# ZGAD250D12.net
KiCad netlist of a schematic drawn in Altium Designer
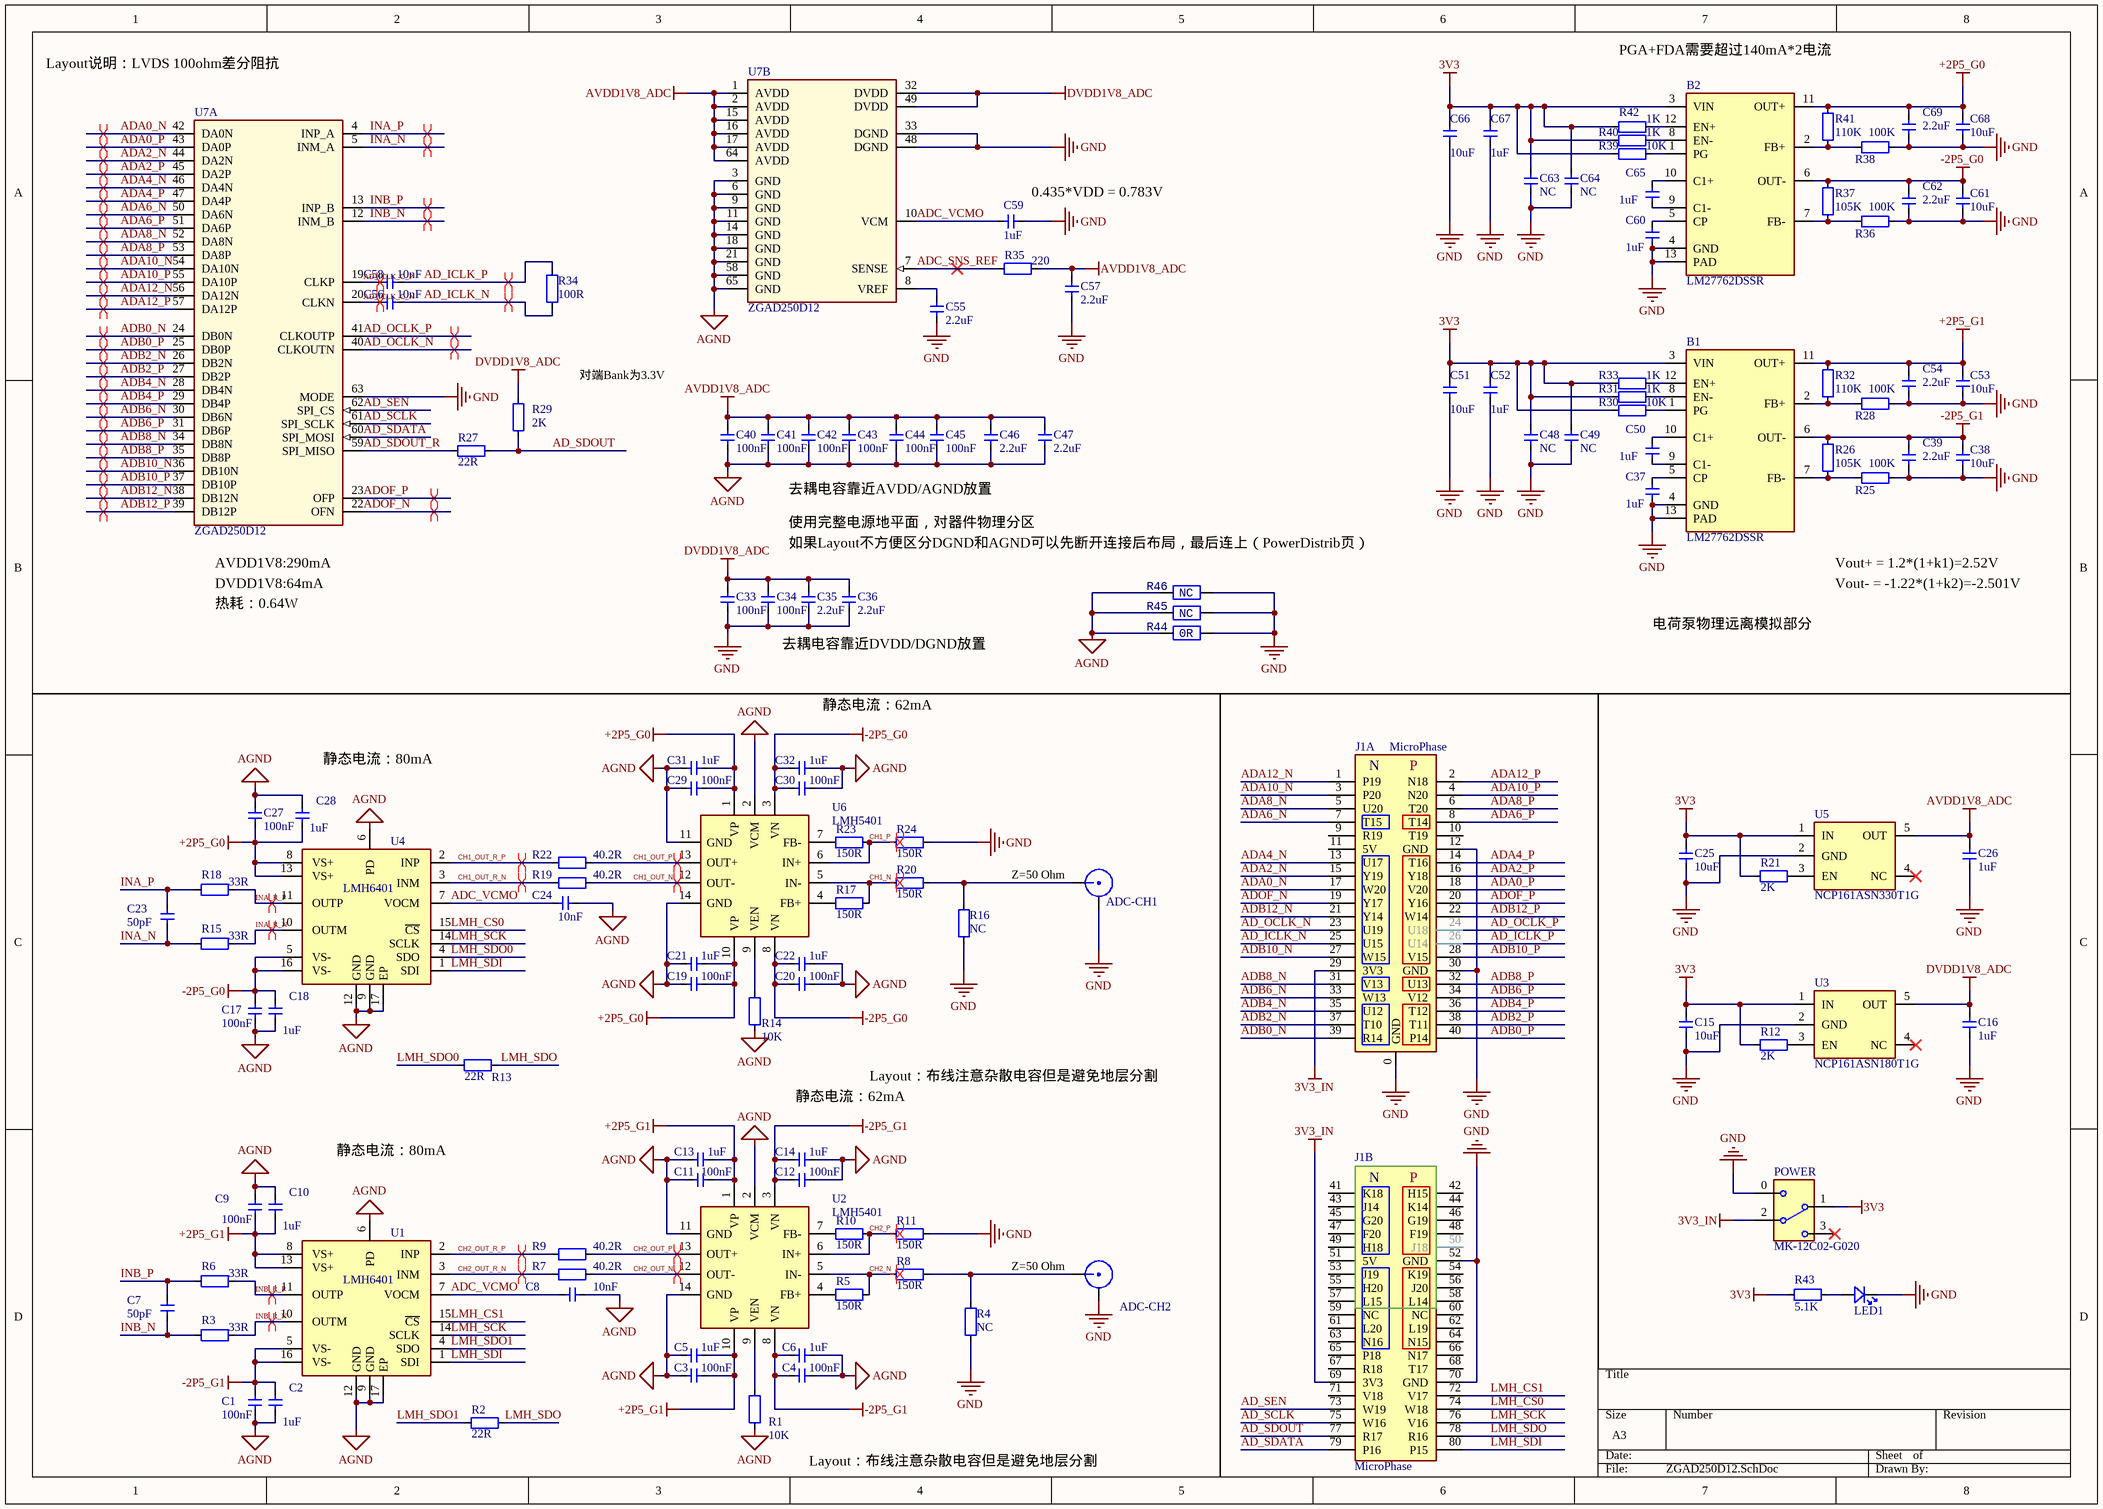
[diagram p0: ZGAD250D12.SchDoc]

(export (version "E")
  (design (tool "Eeschema 10.0.6"))
  (components
    (comp (ref "ADC-CH1")
      (value "SMA")
      (footprint "SMA-KHD")
      (description "SMA射频接口")
      (libsource (lib "Base") (part "SMA"))
    )
    (comp (ref "ADC-CH2")
      (value "SMA")
      (footprint "SMA-KHD")
      (description "SMA射频接口")
      (libsource (lib "Base") (part "SMA"))
    )
    (comp (ref "B1")
      (value "LM27762DSSR")
      (footprint "SON50P200X300X80-13N-D")
      (fields (field (name "MOUSER PART NUMBER") "595-LM27762DSSR"))
      (libsource (lib "Power") (part "LM27762DSSR"))
    )
    (comp (ref "B2")
      (value "LM27762DSSR")
      (footprint "SON50P200X300X80-13N-D")
      (fields (field (name "MOUSER PART NUMBER") "595-LM27762DSSR"))
      (libsource (lib "Power") (part "LM27762DSSR"))
    )
    (comp (ref "C1")
      (value "100nF")
      (footprint "C 0201")
      (description "GRM033Z71C104KE14D")
      (fields (field (name "版权归属") "源创客"))
      (libsource (lib "Base") (part "C"))
    )
    (comp (ref "C2")
      (value "1uF")
      (footprint "C 0402")
      (description "GRM155Z71A105KE01D")
      (fields (field (name "版权归属") "源创客"))
      (libsource (lib "Base") (part "C"))
    )
    (comp (ref "C3")
      (value "100nF")
      (footprint "C 0201")
      (description "GRM033Z71C104KE14D")
      (fields (field (name "版权归属") "源创客"))
      (libsource (lib "Base") (part "C"))
    )
    (comp (ref "C4")
      (value "100nF")
      (footprint "C 0201")
      (description "GRM033Z71C104KE14D")
      (fields (field (name "版权归属") "源创客"))
      (libsource (lib "Base") (part "C"))
    )
    (comp (ref "C5")
      (value "1uF")
      (footprint "C 0402")
      (description "GRM155Z71A105KE01D")
      (fields (field (name "版权归属") "源创客"))
      (libsource (lib "Base") (part "C"))
    )
    (comp (ref "C6")
      (value "1uF")
      (footprint "C 0402")
      (description "GRM155Z71A105KE01D")
      (fields (field (name "版权归属") "源创客"))
      (libsource (lib "Base") (part "C"))
    )
    (comp (ref "C7")
      (value "50pF")
      (footprint "C 0201")
      (description "0603CG500J500NT")
      (fields (field (name "版权归属") "源创客"))
      (libsource (lib "Base") (part "C"))
    )
    (comp (ref "C8")
      (value "10nF")
      (footprint "C 0201")
      (description "0201B103K250NT")
      (fields (field (name "版权归属") "源创客"))
      (libsource (lib "Base") (part "C"))
    )
    (comp (ref "C9")
      (value "100nF")
      (footprint "C 0201")
      (description "GRM033Z71C104KE14D")
      (fields (field (name "版权归属") "源创客"))
      (libsource (lib "Base") (part "C"))
    )
    (comp (ref "C10")
      (value "1uF")
      (footprint "C 0402")
      (description "GRM155Z71A105KE01D")
      (fields (field (name "版权归属") "源创客"))
      (libsource (lib "Base") (part "C"))
    )
    (comp (ref "C11")
      (value "100nF")
      (footprint "C 0201")
      (description "GRM033Z71C104KE14D")
      (fields (field (name "版权归属") "源创客"))
      (libsource (lib "Base") (part "C"))
    )
    (comp (ref "C12")
      (value "100nF")
      (footprint "C 0201")
      (description "GRM033Z71C104KE14D")
      (fields (field (name "版权归属") "源创客"))
      (libsource (lib "Base") (part "C"))
    )
    (comp (ref "C13")
      (value "1uF")
      (footprint "C 0402")
      (description "GRM155Z71A105KE01D")
      (fields (field (name "版权归属") "源创客"))
      (libsource (lib "Base") (part "C"))
    )
    (comp (ref "C14")
      (value "1uF")
      (footprint "C 0402")
      (description "GRM155Z71A105KE01D")
      (fields (field (name "版权归属") "源创客"))
      (libsource (lib "Base") (part "C"))
    )
    (comp (ref "C15")
      (value "10uF")
      (footprint "C 0603")
      (description "无极性贴片电容")
      (fields (field (name "版权归属") "源创客"))
      (libsource (lib "Base") (part "C"))
    )
    (comp (ref "C16")
      (value "1uF")
      (footprint "C 0402")
      (description "无极性贴片电容")
      (fields (field (name "版权归属") "源创客"))
      (libsource (lib "Base") (part "C"))
    )
    (comp (ref "C17")
      (value "100nF")
      (footprint "C 0201")
      (description "GRM033Z71C104KE14D")
      (fields (field (name "版权归属") "源创客"))
      (libsource (lib "Base") (part "C"))
    )
    (comp (ref "C18")
      (value "1uF")
      (footprint "C 0402")
      (description "GRM155Z71A105KE01D")
      (fields (field (name "版权归属") "源创客"))
      (libsource (lib "Base") (part "C"))
    )
    (comp (ref "C19")
      (value "100nF")
      (footprint "C 0201")
      (description "GRM033Z71C104KE14D")
      (fields (field (name "版权归属") "源创客"))
      (libsource (lib "Base") (part "C"))
    )
    (comp (ref "C20")
      (value "100nF")
      (footprint "C 0201")
      (description "GRM033Z71C104KE14D")
      (fields (field (name "版权归属") "源创客"))
      (libsource (lib "Base") (part "C"))
    )
    (comp (ref "C21")
      (value "1uF")
      (footprint "C 0402")
      (description "GRM155Z71A105KE01D")
      (fields (field (name "版权归属") "源创客"))
      (libsource (lib "Base") (part "C"))
    )
    (comp (ref "C22")
      (value "1uF")
      (footprint "C 0402")
      (description "GRM155Z71A105KE01D")
      (fields (field (name "版权归属") "源创客"))
      (libsource (lib "Base") (part "C"))
    )
    (comp (ref "C23")
      (value "50pF")
      (footprint "C 0201")
      (description "0603CG500J500NT")
      (fields (field (name "版权归属") "源创客"))
      (libsource (lib "Base") (part "C"))
    )
    (comp (ref "C24")
      (value "10nF")
      (footprint "C 0201")
      (description "0201B103K250NT")
      (fields (field (name "版权归属") "源创客"))
      (libsource (lib "Base") (part "C"))
    )
    (comp (ref "C25")
      (value "10uF")
      (footprint "C 0603")
      (description "无极性贴片电容")
      (fields (field (name "版权归属") "源创客"))
      (libsource (lib "Base") (part "C"))
    )
    (comp (ref "C26")
      (value "1uF")
      (footprint "C 0402")
      (description "无极性贴片电容")
      (fields (field (name "版权归属") "源创客"))
      (libsource (lib "Base") (part "C"))
    )
    (comp (ref "C27")
      (value "100nF")
      (footprint "C 0201")
      (description "GRM033Z71C104KE14D")
      (fields (field (name "版权归属") "源创客"))
      (libsource (lib "Base") (part "C"))
    )
    (comp (ref "C28")
      (value "1uF")
      (footprint "C 0402")
      (description "GRM155Z71A105KE01D")
      (fields (field (name "版权归属") "源创客"))
      (libsource (lib "Base") (part "C"))
    )
    (comp (ref "C29")
      (value "100nF")
      (footprint "C 0201")
      (description "GRM033Z71C104KE14D")
      (fields (field (name "版权归属") "源创客"))
      (libsource (lib "Base") (part "C"))
    )
    (comp (ref "C30")
      (value "100nF")
      (footprint "C 0201")
      (description "GRM033Z71C104KE14D")
      (fields (field (name "版权归属") "源创客"))
      (libsource (lib "Base") (part "C"))
    )
    (comp (ref "C31")
      (value "1uF")
      (footprint "C 0402")
      (description "GRM155Z71A105KE01D")
      (fields (field (name "版权归属") "源创客"))
      (libsource (lib "Base") (part "C"))
    )
    (comp (ref "C32")
      (value "1uF")
      (footprint "C 0402")
      (description "GRM155Z71A105KE01D")
      (fields (field (name "版权归属") "源创客"))
      (libsource (lib "Base") (part "C"))
    )
    (comp (ref "C33")
      (value "100nF")
      (footprint "C 0201")
      (description "GRM033Z71C104KE14D")
      (fields (field (name "版权归属") "源创客"))
      (libsource (lib "Base") (part "C"))
    )
    (comp (ref "C34")
      (value "100nF")
      (footprint "C 0201")
      (description "GRM033Z71C104KE14D")
      (fields (field (name "版权归属") "源创客"))
      (libsource (lib "Base") (part "C"))
    )
    (comp (ref "C35")
      (value "2.2uF")
      (footprint "C 0603")
      (description "0603B225K250NT")
      (fields (field (name "版权归属") "源创客"))
      (libsource (lib "Base") (part "C"))
    )
    (comp (ref "C36")
      (value "2.2uF")
      (footprint "C 0603")
      (description "0603B225K250NT")
      (fields (field (name "版权归属") "源创客"))
      (libsource (lib "Base") (part "C"))
    )
    (comp (ref "C37")
      (value "1uF")
      (footprint "C 0402")
      (description "GRM155Z71A105KE01D")
      (fields (field (name "版权归属") "源创客"))
      (libsource (lib "Base") (part "C"))
    )
    (comp (ref "C38")
      (value "10uF")
      (footprint "C 0603")
      (description "GRM188Z71A106KA73D")
      (fields (field (name "版权归属") "源创客"))
      (libsource (lib "Base") (part "C"))
    )
    (comp (ref "C39")
      (value "2.2uF")
      (footprint "C 0402")
      (description "GRM155Z71A225KE44D")
      (fields (field (name "版权归属") "源创客"))
      (libsource (lib "Base") (part "C"))
    )
    (comp (ref "C40")
      (value "100nF")
      (footprint "C 0201")
      (description "GRM033Z71C104KE14D")
      (fields (field (name "版权归属") "源创客"))
      (libsource (lib "Base") (part "C"))
    )
    (comp (ref "C41")
      (value "100nF")
      (footprint "C 0201")
      (description "GRM033Z71C104KE14D")
      (fields (field (name "版权归属") "源创客"))
      (libsource (lib "Base") (part "C"))
    )
    (comp (ref "C42")
      (value "100nF")
      (footprint "C 0201")
      (description "GRM033Z71C104KE14D")
      (fields (field (name "版权归属") "源创客"))
      (libsource (lib "Base") (part "C"))
    )
    (comp (ref "C43")
      (value "100nF")
      (footprint "C 0201")
      (description "GRM033Z71C104KE14D")
      (fields (field (name "版权归属") "源创客"))
      (libsource (lib "Base") (part "C"))
    )
    (comp (ref "C44")
      (value "100nF")
      (footprint "C 0201")
      (description "GRM033Z71C104KE14D")
      (fields (field (name "版权归属") "源创客"))
      (libsource (lib "Base") (part "C"))
    )
    (comp (ref "C45")
      (value "100nF")
      (footprint "C 0201")
      (description "GRM033Z71C104KE14D")
      (fields (field (name "版权归属") "源创客"))
      (libsource (lib "Base") (part "C"))
    )
    (comp (ref "C46")
      (value "2.2uF")
      (footprint "C 0603")
      (description "0603B225K250NT")
      (fields (field (name "版权归属") "源创客"))
      (libsource (lib "Base") (part "C"))
    )
    (comp (ref "C47")
      (value "2.2uF")
      (footprint "C 0603")
      (description "0603B225K250NT")
      (fields (field (name "版权归属") "源创客"))
      (libsource (lib "Base") (part "C"))
    )
    (comp (ref "C48")
      (value "NC")
      (footprint "C 0201")
      (description "GRM033Z71C104KE14D")
      (fields (field (name "版权归属") "源创客"))
      (libsource (lib "Base") (part "C"))
    )
    (comp (ref "C49")
      (value "NC")
      (footprint "C 0201")
      (description "GRM033Z71C104KE14D")
      (fields (field (name "版权归属") "源创客"))
      (libsource (lib "Base") (part "C"))
    )
    (comp (ref "C50")
      (value "1uF")
      (footprint "C 0402")
      (description "GRM155Z71A105KE01D")
      (fields (field (name "版权归属") "源创客"))
      (libsource (lib "Base") (part "C"))
    )
    (comp (ref "C51")
      (value "10uF")
      (footprint "C 0603")
      (description "GRM188Z71A106KA73D")
      (fields (field (name "版权归属") "源创客"))
      (libsource (lib "Base") (part "C"))
    )
    (comp (ref "C52")
      (value "1uF")
      (footprint "C 0402")
      (description "GRM155Z71A105KE01D")
      (fields (field (name "版权归属") "源创客"))
      (libsource (lib "Base") (part "C"))
    )
    (comp (ref "C53")
      (value "10uF")
      (footprint "C 0603")
      (description "GRM188Z71A106KA73D")
      (fields (field (name "版权归属") "源创客"))
      (libsource (lib "Base") (part "C"))
    )
    (comp (ref "C54")
      (value "2.2uF")
      (footprint "C 0402")
      (description "GRM155Z71A225KE44D")
      (fields (field (name "版权归属") "源创客"))
      (libsource (lib "Base") (part "C"))
    )
    (comp (ref "C55")
      (value "2.2uF")
      (footprint "C 0603")
      (description "0603B225K250NT")
      (fields (field (name "版权归属") "源创客"))
      (libsource (lib "Base") (part "C"))
    )
    (comp (ref "C56")
      (value "10nF")
      (footprint "C 0201")
      (description "0201B103K250NT")
      (fields (field (name "版权归属") "源创客"))
      (libsource (lib "Base") (part "C"))
    )
    (comp (ref "C57")
      (value "2.2uF")
      (footprint "C 0603")
      (description "0603B225K250NT")
      (fields (field (name "版权归属") "源创客"))
      (libsource (lib "Base") (part "C"))
    )
    (comp (ref "C58")
      (value "10nF")
      (footprint "C 0201")
      (description "0201B103K250NT")
      (fields (field (name "版权归属") "源创客"))
      (libsource (lib "Base") (part "C"))
    )
    (comp (ref "C59")
      (value "1uF")
      (footprint "C 0402")
      (description "GRM155Z71A105KE01D")
      (fields (field (name "版权归属") "源创客"))
      (libsource (lib "Base") (part "C"))
    )
    (comp (ref "C60")
      (value "1uF")
      (footprint "C 0402")
      (description "GRM155Z71A105KE01D")
      (fields (field (name "版权归属") "源创客"))
      (libsource (lib "Base") (part "C"))
    )
    (comp (ref "C61")
      (value "10uF")
      (footprint "C 0603")
      (description "GRM188Z71A106KA73D")
      (fields (field (name "版权归属") "源创客"))
      (libsource (lib "Base") (part "C"))
    )
    (comp (ref "C62")
      (value "2.2uF")
      (footprint "C 0402")
      (description "GRM155Z71A225KE44D")
      (fields (field (name "版权归属") "源创客"))
      (libsource (lib "Base") (part "C"))
    )
    (comp (ref "C63")
      (value "NC")
      (footprint "C 0201")
      (description "GRM033Z71C104KE14D")
      (fields (field (name "版权归属") "源创客"))
      (libsource (lib "Base") (part "C"))
    )
    (comp (ref "C64")
      (value "NC")
      (footprint "C 0201")
      (description "GRM033Z71C104KE14D")
      (fields (field (name "版权归属") "源创客"))
      (libsource (lib "Base") (part "C"))
    )
    (comp (ref "C65")
      (value "1uF")
      (footprint "C 0402")
      (description "GRM155Z71A105KE01D")
      (fields (field (name "版权归属") "源创客"))
      (libsource (lib "Base") (part "C"))
    )
    (comp (ref "C66")
      (value "10uF")
      (footprint "C 0603")
      (description "GRM188Z71A106KA73D")
      (fields (field (name "版权归属") "源创客"))
      (libsource (lib "Base") (part "C"))
    )
    (comp (ref "C67")
      (value "1uF")
      (footprint "C 0402")
      (description "GRM155Z71A105KE01D")
      (fields (field (name "版权归属") "源创客"))
      (libsource (lib "Base") (part "C"))
    )
    (comp (ref "C68")
      (value "10uF")
      (footprint "C 0603")
      (description "GRM188Z71A106KA73D")
      (fields (field (name "版权归属") "源创客"))
      (libsource (lib "Base") (part "C"))
    )
    (comp (ref "C69")
      (value "2.2uF")
      (footprint "C 0402")
      (description "GRM155Z71A225KE44D")
      (fields (field (name "版权归属") "源创客"))
      (libsource (lib "Base") (part "C"))
    )
    (comp (ref "J1")
      (value "MicroPhase")
      (footprint "MicroPhase")
      (description "MicroPhase DIP接口")
      (libsource (lib "Base") (part "MicroPhase"))
    )
    (comp (ref "LED1")
      (value "LED-SMD")
      (footprint "LED 0603W")
      (description "贴片LED")
      (fields (field (name "版权归属") "源创客"))
      (libsource (lib "Base") (part "LED-SMD"))
    )
    (comp (ref "POWER")
      (value "MK-12C02-G020")
      (footprint "MSK-12C01-07")
      (fields (field (name "版权归属") "源创客"))
      (libsource (lib "Base") (part "Switch-1CH-SMD_1"))
    )
    (comp (ref "R1")
      (value "10K")
      (footprint "R 0201")
      (description "贴片电阻")
      (fields (field (name "版权归属") "源创客"))
      (libsource (lib "") (part "R_3"))
    )
    (comp (ref "R2")
      (value "22R")
      (footprint "R 0201")
      (description "贴片电阻")
      (fields (field (name "版权归属") "源创客"))
      (libsource (lib "") (part "R_1"))
    )
    (comp (ref "R3")
      (value "33R")
      (footprint "R 0402")
      (description "贴片电阻")
      (fields (field (name "版权归属") "源创客"))
      (libsource (lib "") (part "R_1"))
    )
    (comp (ref "R4")
      (value "NC")
      (footprint "R 0201")
      (description "贴片电阻")
      (fields (field (name "版权归属") "源创客"))
      (libsource (lib "") (part "R_2"))
    )
    (comp (ref "R5")
      (value "150R")
      (footprint "R 0201")
      (description "贴片电阻")
      (fields (field (name "版权归属") "源创客"))
      (libsource (lib "") (part "R_1"))
    )
    (comp (ref "R6")
      (value "33R")
      (footprint "R 0402")
      (description "贴片电阻")
      (fields (field (name "版权归属") "源创客"))
      (libsource (lib "") (part "R_1"))
    )
    (comp (ref "R7")
      (value "40.2R")
      (footprint "R 0201")
      (description "贴片电阻")
      (fields (field (name "版权归属") "源创客"))
      (libsource (lib "") (part "R_1"))
    )
    (comp (ref "R8")
      (value "150R")
      (footprint "R 0201")
      (description "贴片电阻")
      (fields (field (name "版权归属") "源创客"))
      (libsource (lib "") (part "R_1"))
    )
    (comp (ref "R9")
      (value "40.2R")
      (footprint "R 0201")
      (description "贴片电阻")
      (fields (field (name "版权归属") "源创客"))
      (libsource (lib "") (part "R_1"))
    )
    (comp (ref "R10")
      (value "150R")
      (footprint "R 0201")
      (description "贴片电阻")
      (fields (field (name "版权归属") "源创客"))
      (libsource (lib "") (part "R_1"))
    )
    (comp (ref "R11")
      (value "150R")
      (footprint "R 0201")
      (description "贴片电阻")
      (fields (field (name "版权归属") "源创客"))
      (libsource (lib "Base") (part "R"))
    )
    (comp (ref "R12")
      (value "2K")
      (footprint "R 0402")
      (description "贴片电阻")
      (fields (field (name "版权归属") "源创客"))
      (libsource (lib "") (part "R_2"))
    )
    (comp (ref "R13")
      (value "22R")
      (footprint "R 0201")
      (description "贴片电阻")
      (fields (field (name "版权归属") "源创客"))
      (libsource (lib "") (part "R_1"))
    )
    (comp (ref "R14")
      (value "10K")
      (footprint "R 0201")
      (description "贴片电阻")
      (fields (field (name "版权归属") "源创客"))
      (libsource (lib "") (part "R_3"))
    )
    (comp (ref "R15")
      (value "33R")
      (footprint "R 0402")
      (description "贴片电阻")
      (fields (field (name "版权归属") "源创客"))
      (libsource (lib "") (part "R_1"))
    )
    (comp (ref "R16")
      (value "NC")
      (footprint "R 0201")
      (description "贴片电阻")
      (fields (field (name "版权归属") "源创客"))
      (libsource (lib "") (part "R_2"))
    )
    (comp (ref "R17")
      (value "150R")
      (footprint "R 0201")
      (description "贴片电阻")
      (fields (field (name "版权归属") "源创客"))
      (libsource (lib "") (part "R_1"))
    )
    (comp (ref "R18")
      (value "33R")
      (footprint "R 0402")
      (description "贴片电阻")
      (fields (field (name "版权归属") "源创客"))
      (libsource (lib "") (part "R_1"))
    )
    (comp (ref "R19")
      (value "40.2R")
      (footprint "R 0201")
      (description "贴片电阻")
      (fields (field (name "版权归属") "源创客"))
      (libsource (lib "") (part "R_1"))
    )
    (comp (ref "R20")
      (value "150R")
      (footprint "R 0201")
      (description "贴片电阻")
      (fields (field (name "版权归属") "源创客"))
      (libsource (lib "") (part "R_1"))
    )
    (comp (ref "R21")
      (value "2K")
      (footprint "R 0402")
      (description "贴片电阻")
      (fields (field (name "版权归属") "源创客"))
      (libsource (lib "") (part "R_2"))
    )
    (comp (ref "R22")
      (value "40.2R")
      (footprint "R 0201")
      (description "贴片电阻")
      (fields (field (name "版权归属") "源创客"))
      (libsource (lib "") (part "R_1"))
    )
    (comp (ref "R23")
      (value "150R")
      (footprint "R 0201")
      (description "贴片电阻")
      (fields (field (name "版权归属") "源创客"))
      (libsource (lib "") (part "R_1"))
    )
    (comp (ref "R24")
      (value "150R")
      (footprint "R 0201")
      (description "贴片电阻")
      (fields (field (name "版权归属") "源创客"))
      (libsource (lib "Base") (part "R"))
    )
    (comp (ref "R25")
      (value "100K")
      (footprint "R 0402")
      (description "贴片电阻")
      (fields (field (name "版权归属") "源创客"))
      (libsource (lib "") (part "R_2"))
    )
    (comp (ref "R26")
      (value "105K")
      (footprint "R 0402")
      (description "贴片电阻")
      (fields (field (name "版权归属") "源创客"))
      (libsource (lib "Base") (part "R"))
    )
    (comp (ref "R27")
      (value "22R")
      (footprint "R 0201")
      (description "贴片电阻")
      (fields (field (name "版权归属") "源创客"))
      (libsource (lib "") (part "R_1"))
    )
    (comp (ref "R28")
      (value "100K")
      (footprint "R 0402")
      (description "贴片电阻")
      (fields (field (name "版权归属") "源创客"))
      (libsource (lib "") (part "R_2"))
    )
    (comp (ref "R29")
      (value "2K")
      (footprint "R 0201")
      (description "贴片电阻")
      (fields (field (name "版权归属") "源创客"))
      (libsource (lib "") (part "R_2"))
    )
    (comp (ref "R30")
      (value "10K")
      (footprint "R 0402")
      (description "贴片电阻")
      (fields (field (name "版权归属") "源创客"))
      (libsource (lib "") (part "R_3"))
    )
    (comp (ref "R31")
      (value "1K")
      (footprint "R 0402")
      (description "贴片电阻")
      (fields (field (name "版权归属") "源创客"))
      (libsource (lib "") (part "R_3"))
    )
    (comp (ref "R32")
      (value "110K")
      (footprint "R 0402")
      (description "贴片电阻")
      (fields (field (name "版权归属") "源创客"))
      (libsource (lib "Base") (part "R"))
    )
    (comp (ref "R33")
      (value "1K")
      (footprint "R 0402")
      (description "贴片电阻")
      (fields (field (name "版权归属") "源创客"))
      (libsource (lib "") (part "R_3"))
    )
    (comp (ref "R34")
      (value "100R")
      (footprint "R 0201")
      (description "贴片电阻")
      (fields (field (name "版权归属") "源创客"))
      (libsource (lib "") (part "R_3"))
    )
    (comp (ref "R35")
      (value "220")
      (footprint "R 0201")
      (description "贴片电阻")
      (fields (field (name "版权归属") "源创客"))
      (libsource (lib "Base") (part "R"))
    )
    (comp (ref "R36")
      (value "100K")
      (footprint "R 0402")
      (description "贴片电阻")
      (fields (field (name "版权归属") "源创客"))
      (libsource (lib "") (part "R_2"))
    )
    (comp (ref "R37")
      (value "105K")
      (footprint "R 0402")
      (description "贴片电阻")
      (fields (field (name "版权归属") "源创客"))
      (libsource (lib "Base") (part "R"))
    )
    (comp (ref "R38")
      (value "100K")
      (footprint "R 0402")
      (description "贴片电阻")
      (fields (field (name "版权归属") "源创客"))
      (libsource (lib "") (part "R_2"))
    )
    (comp (ref "R39")
      (value "10K")
      (footprint "R 0402")
      (description "贴片电阻")
      (fields (field (name "版权归属") "源创客"))
      (libsource (lib "") (part "R_3"))
    )
    (comp (ref "R40")
      (value "1K")
      (footprint "R 0402")
      (description "贴片电阻")
      (fields (field (name "版权归属") "源创客"))
      (libsource (lib "") (part "R_3"))
    )
    (comp (ref "R41")
      (value "110K")
      (footprint "R 0402")
      (description "贴片电阻")
      (fields (field (name "版权归属") "源创客"))
      (libsource (lib "Base") (part "R"))
    )
    (comp (ref "R42")
      (value "1K")
      (footprint "R 0402")
      (description "贴片电阻")
      (fields (field (name "版权归属") "源创客"))
      (libsource (lib "") (part "R_3"))
    )
    (comp (ref "R43")
      (value "5.1K")
      (footprint "R 0402")
      (description "贴片电阻")
      (fields (field (name "版权归属") "源创客"))
      (libsource (lib "") (part "R_3"))
    )
    (comp (ref "R44")
      (value "0R")
      (footprint "R_0603")
      (description "Chip Resistor 0R Jumper 0603, 1A")
      (fields (field (name "TOLERANCE") "Jumper") (field (name "MANUFACTURE PARTNUMBER") "AC0603JR-070RL"))
      (libsource (lib "Database_Libs1") (part "Res"))
    )
    (comp (ref "R45")
      (value "NC")
      (footprint "R_0603")
      (description "Chip Resistor 0R Jumper 0603, 1A")
      (fields (field (name "TOLERANCE") "Jumper") (field (name "MANUFACTURE PARTNUMBER") "AC0603JR-070RL"))
      (libsource (lib "Database_Libs1") (part "Res"))
    )
    (comp (ref "R46")
      (value "NC")
      (footprint "R_0603")
      (description "Chip Resistor 0R Jumper 0603, 1A")
      (fields (field (name "TOLERANCE") "Jumper") (field (name "MANUFACTURE PARTNUMBER") "AC0603JR-070RL"))
      (libsource (lib "Database_Libs1") (part "Res"))
    )
    (comp (ref "U1")
      (value "LMH6401")
      (footprint "LMH6401IRMZT")
      (description "4.5 GHz Ultra Wideband Digital Variable Gain Amplifier")
      (fields
        (field (name "MOUSER PART NUMBER") "595-LMH6401IRMZT")
        (field (name "MANUFACTURER_PART_NUMBER") "LMH6401IRMZT")
      )
      (libsource (lib "Chip") (part "LMH6401"))
    )
    (comp (ref "U2")
      (value "LMH5401")
      (footprint "LMH5401IRMSR")
      (description "8-GHz, Low-Noise, Low-Power, Fully-Differential Amplifier")
      (fields (field (name "版权归属") "源创客"))
      (libsource (lib "Chip") (part "LMH5401"))
    )
    (comp (ref "U3")
      (value "NCP161ASN180T1G")
      (footprint "SOT23-5L")
      (libsource (lib "Chip") (part "NCP161ASN500T1G"))
    )
    (comp (ref "U4")
      (value "LMH6401")
      (footprint "LMH6401IRMZT")
      (description "4.5 GHz Ultra Wideband Digital Variable Gain Amplifier")
      (fields
        (field (name "MOUSER PART NUMBER") "595-LMH6401IRMZT")
        (field (name "MANUFACTURER_PART_NUMBER") "LMH6401IRMZT")
      )
      (libsource (lib "Chip") (part "LMH6401"))
    )
    (comp (ref "U5")
      (value "NCP161ASN330T1G")
      (footprint "SOT23-5L")
      (libsource (lib "Chip") (part "NCP161ASN500T1G"))
    )
    (comp (ref "U6")
      (value "LMH5401")
      (footprint "LMH5401IRMSR")
      (description "8-GHz, Low-Noise, Low-Power, Fully-Differential Amplifier")
      (fields (field (name "版权归属") "源创客"))
      (libsource (lib "Chip") (part "LMH5401"))
    )
    (comp (ref "U7")
      (value "ZGAD250D12")
      (footprint "QFN64 9x9_L")
      (description "双通道 12 位 250Msps 的\r\n模数转换器（ADC）")
      (libsource (lib "Chip") (part "ZGAD250D12"))
    )
  )
  (nets
    (net (code "1") (name "+2P5_G0") (class "Default")
      (node (ref "B2") (pin "11") (pinfunction "OUT+_11") (pintype "power_in"))
      (node (ref "C19") (pin "1") (pinfunction "1_1") (pintype "passive"))
      (node (ref "C21") (pin "1") (pinfunction "1_1") (pintype "passive"))
      (node (ref "C27") (pin "1") (pinfunction "1_1") (pintype "passive"))
      (node (ref "C28") (pin "1") (pinfunction "1_1") (pintype "passive"))
      (node (ref "C29") (pin "1") (pinfunction "1_1") (pintype "passive"))
      (node (ref "C31") (pin "1") (pinfunction "1_1") (pintype "passive"))
      (node (ref "C68") (pin "2") (pinfunction "2_2") (pintype "passive"))
      (node (ref "C69") (pin "2") (pinfunction "2_2") (pintype "passive"))
      (node (ref "R41") (pin "2") (pinfunction "2_2") (pintype "passive"))
      (node (ref "U4") (pin "13") (pinfunction "VS+_13") (pintype "passive"))
      (node (ref "U4") (pin "8") (pinfunction "VS+_8") (pintype "passive"))
      (node (ref "U6") (pin "1") (pinfunction "VP_1") (pintype "passive"))
      (node (ref "U6") (pin "10") (pinfunction "VP_10") (pintype "passive"))
    )
    (net (code "2") (name "+2P5_G1") (class "Default")
      (node (ref "B1") (pin "11") (pinfunction "OUT+_11") (pintype "power_in"))
      (node (ref "C10") (pin "1") (pinfunction "1_1") (pintype "passive"))
      (node (ref "C11") (pin "1") (pinfunction "1_1") (pintype "passive"))
      (node (ref "C13") (pin "1") (pinfunction "1_1") (pintype "passive"))
      (node (ref "C3") (pin "1") (pinfunction "1_1") (pintype "passive"))
      (node (ref "C5") (pin "1") (pinfunction "1_1") (pintype "passive"))
      (node (ref "C53") (pin "2") (pinfunction "2_2") (pintype "passive"))
      (node (ref "C54") (pin "2") (pinfunction "2_2") (pintype "passive"))
      (node (ref "C9") (pin "1") (pinfunction "1_1") (pintype "passive"))
      (node (ref "R32") (pin "2") (pinfunction "2_2") (pintype "passive"))
      (node (ref "U1") (pin "13") (pinfunction "VS+_13") (pintype "passive"))
      (node (ref "U1") (pin "8") (pinfunction "VS+_8") (pintype "passive"))
      (node (ref "U2") (pin "1") (pinfunction "VP_1") (pintype "passive"))
      (node (ref "U2") (pin "10") (pinfunction "VP_10") (pintype "passive"))
    )
    (net (code "3") (name "-2P5_G0") (class "Default")
      (node (ref "B2") (pin "6") (pinfunction "OUT-_6") (pintype "power_in"))
      (node (ref "C17") (pin "2") (pinfunction "2_2") (pintype "passive"))
      (node (ref "C18") (pin "2") (pinfunction "2_2") (pintype "passive"))
      (node (ref "C20") (pin "2") (pinfunction "2_2") (pintype "passive"))
      (node (ref "C22") (pin "2") (pinfunction "2_2") (pintype "passive"))
      (node (ref "C30") (pin "2") (pinfunction "2_2") (pintype "passive"))
      (node (ref "C32") (pin "2") (pinfunction "2_2") (pintype "passive"))
      (node (ref "C61") (pin "2") (pinfunction "2_2") (pintype "passive"))
      (node (ref "C62") (pin "2") (pinfunction "2_2") (pintype "passive"))
      (node (ref "R37") (pin "2") (pinfunction "2_2") (pintype "passive"))
      (node (ref "U4") (pin "16") (pinfunction "VS-_16") (pintype "passive"))
      (node (ref "U4") (pin "5") (pinfunction "VS-_5") (pintype "passive"))
      (node (ref "U6") (pin "3") (pinfunction "VN_3") (pintype "passive"))
      (node (ref "U6") (pin "8") (pinfunction "VN_8") (pintype "passive"))
    )
    (net (code "4") (name "-2P5_G1") (class "Default")
      (node (ref "B1") (pin "6") (pinfunction "OUT-_6") (pintype "power_in"))
      (node (ref "C1") (pin "2") (pinfunction "2_2") (pintype "passive"))
      (node (ref "C12") (pin "2") (pinfunction "2_2") (pintype "passive"))
      (node (ref "C14") (pin "2") (pinfunction "2_2") (pintype "passive"))
      (node (ref "C2") (pin "2") (pinfunction "2_2") (pintype "passive"))
      (node (ref "C38") (pin "2") (pinfunction "2_2") (pintype "passive"))
      (node (ref "C39") (pin "2") (pinfunction "2_2") (pintype "passive"))
      (node (ref "C4") (pin "2") (pinfunction "2_2") (pintype "passive"))
      (node (ref "C6") (pin "2") (pinfunction "2_2") (pintype "passive"))
      (node (ref "R26") (pin "2") (pinfunction "2_2") (pintype "passive"))
      (node (ref "U1") (pin "16") (pinfunction "VS-_16") (pintype "passive"))
      (node (ref "U1") (pin "5") (pinfunction "VS-_5") (pintype "passive"))
      (node (ref "U2") (pin "3") (pinfunction "VN_3") (pintype "passive"))
      (node (ref "U2") (pin "8") (pinfunction "VN_8") (pintype "passive"))
    )
    (net (code "5") (name "/ADA0_N") (class "Default")
      (node (ref "J1") (pin "17") (pinfunction "W20_17") (pintype "passive"))
      (node (ref "U7") (pin "42") (pinfunction "DA0N_42") (pintype "passive"))
    )
    (net (code "6") (name "/ADA0_P") (class "Default")
      (node (ref "J1") (pin "18") (pinfunction "V20_18") (pintype "passive"))
      (node (ref "U7") (pin "43") (pinfunction "DA0P_43") (pintype "passive"))
    )
    (net (code "7") (name "/ADA2_N") (class "Default")
      (node (ref "J1") (pin "15") (pinfunction "Y19_15") (pintype "passive"))
      (node (ref "U7") (pin "44") (pinfunction "DA2N_44") (pintype "passive"))
    )
    (net (code "8") (name "/ADA2_P") (class "Default")
      (node (ref "J1") (pin "16") (pinfunction "Y18_16") (pintype "passive"))
      (node (ref "U7") (pin "45") (pinfunction "DA2P_45") (pintype "passive"))
    )
    (net (code "9") (name "/ADA4_N") (class "Default")
      (node (ref "J1") (pin "13") (pinfunction "U17_13") (pintype "passive"))
      (node (ref "U7") (pin "46") (pinfunction "DA4N_46") (pintype "passive"))
    )
    (net (code "10") (name "/ADA4_P") (class "Default")
      (node (ref "J1") (pin "14") (pinfunction "T16_14") (pintype "passive"))
      (node (ref "U7") (pin "47") (pinfunction "DA4P_47") (pintype "passive"))
    )
    (net (code "11") (name "/ADA6_N") (class "Default")
      (node (ref "J1") (pin "7") (pinfunction "T15_7") (pintype "passive"))
      (node (ref "U7") (pin "50") (pinfunction "DA6N_50") (pintype "passive"))
    )
    (net (code "12") (name "/ADA6_P") (class "Default")
      (node (ref "J1") (pin "8") (pinfunction "T14_8") (pintype "passive"))
      (node (ref "U7") (pin "51") (pinfunction "DA6P_51") (pintype "passive"))
    )
    (net (code "13") (name "/ADA8_N") (class "Default")
      (node (ref "J1") (pin "5") (pinfunction "U20_5") (pintype "passive"))
      (node (ref "U7") (pin "52") (pinfunction "DA8N_52") (pintype "passive"))
    )
    (net (code "14") (name "/ADA8_P") (class "Default")
      (node (ref "J1") (pin "6") (pinfunction "T20_6") (pintype "passive"))
      (node (ref "U7") (pin "53") (pinfunction "DA8P_53") (pintype "passive"))
    )
    (net (code "15") (name "/ADA10_N") (class "Default")
      (node (ref "J1") (pin "3") (pinfunction "P20_3") (pintype "passive"))
      (node (ref "U7") (pin "54") (pinfunction "DA10N_54") (pintype "passive"))
    )
    (net (code "16") (name "/ADA10_P") (class "Default")
      (node (ref "J1") (pin "4") (pinfunction "N20_4") (pintype "passive"))
      (node (ref "U7") (pin "55") (pinfunction "DA10P_55") (pintype "passive"))
    )
    (net (code "17") (name "/ADA12_N") (class "Default")
      (node (ref "J1") (pin "1") (pinfunction "P19_1") (pintype "passive"))
      (node (ref "U7") (pin "56") (pinfunction "DA12N_56") (pintype "passive"))
    )
    (net (code "18") (name "/ADA12_P") (class "Default")
      (node (ref "J1") (pin "2") (pinfunction "N18_2") (pintype "passive"))
      (node (ref "U7") (pin "57") (pinfunction "DA12P_57") (pintype "passive"))
    )
    (net (code "19") (name "/ADB0_N") (class "Default")
      (node (ref "J1") (pin "39") (pinfunction "R14_39") (pintype "passive"))
      (node (ref "U7") (pin "24") (pinfunction "DB0N_24") (pintype "passive"))
    )
    (net (code "20") (name "/ADB0_P") (class "Default")
      (node (ref "J1") (pin "40") (pinfunction "P14_40") (pintype "passive"))
      (node (ref "U7") (pin "25") (pinfunction "DB0P_25") (pintype "passive"))
    )
    (net (code "21") (name "/ADB2_N") (class "Default")
      (node (ref "J1") (pin "37") (pinfunction "T10_37") (pintype "passive"))
      (node (ref "U7") (pin "26") (pinfunction "DB2N_26") (pintype "passive"))
    )
    (net (code "22") (name "/ADB2_P") (class "Default")
      (node (ref "J1") (pin "38") (pinfunction "T11_38") (pintype "passive"))
      (node (ref "U7") (pin "27") (pinfunction "DB2P_27") (pintype "passive"))
    )
    (net (code "23") (name "/ADB4_N") (class "Default")
      (node (ref "J1") (pin "35") (pinfunction "U12_35") (pintype "passive"))
      (node (ref "U7") (pin "28") (pinfunction "DB4N_28") (pintype "passive"))
    )
    (net (code "24") (name "/ADB4_P") (class "Default")
      (node (ref "J1") (pin "36") (pinfunction "T12_36") (pintype "passive"))
      (node (ref "U7") (pin "29") (pinfunction "DB4P_29") (pintype "passive"))
    )
    (net (code "25") (name "/ADB6_N") (class "Default")
      (node (ref "J1") (pin "33") (pinfunction "W13_33") (pintype "passive"))
      (node (ref "U7") (pin "30") (pinfunction "DB6N_30") (pintype "passive"))
    )
    (net (code "26") (name "/ADB6_P") (class "Default")
      (node (ref "J1") (pin "34") (pinfunction "V12_34") (pintype "passive"))
      (node (ref "U7") (pin "31") (pinfunction "DB6P_31") (pintype "passive"))
    )
    (net (code "27") (name "/ADB8_N") (class "Default")
      (node (ref "J1") (pin "31") (pinfunction "V13_31") (pintype "passive"))
      (node (ref "U7") (pin "34") (pinfunction "DB8N_34") (pintype "passive"))
    )
    (net (code "28") (name "/ADB8_P") (class "Default")
      (node (ref "J1") (pin "32") (pinfunction "U13_32") (pintype "passive"))
      (node (ref "U7") (pin "35") (pinfunction "DB8P_35") (pintype "passive"))
    )
    (net (code "29") (name "/ADB10_N") (class "Default")
      (node (ref "J1") (pin "27") (pinfunction "W15_27") (pintype "passive"))
      (node (ref "U7") (pin "36") (pinfunction "DB10N_36") (pintype "passive"))
    )
    (net (code "30") (name "/ADB10_P") (class "Default")
      (node (ref "J1") (pin "28") (pinfunction "V15_28") (pintype "passive"))
      (node (ref "U7") (pin "37") (pinfunction "DB10P_37") (pintype "passive"))
    )
    (net (code "31") (name "/ADB12_N") (class "Default")
      (node (ref "J1") (pin "21") (pinfunction "Y14_21") (pintype "passive"))
      (node (ref "U7") (pin "38") (pinfunction "DB12N_38") (pintype "passive"))
    )
    (net (code "32") (name "/ADB12_P") (class "Default")
      (node (ref "J1") (pin "22") (pinfunction "W14_22") (pintype "passive"))
      (node (ref "U7") (pin "39") (pinfunction "DB12P_39") (pintype "passive"))
    )
    (net (code "33") (name "/ADC_SNS_REF") (class "Default")
      (node (ref "R35") (pin "1") (pinfunction "1_1") (pintype "passive"))
      (node (ref "U7") (pin "7") (pinfunction "SENSE_7") (pintype "input"))
    )
    (net (code "34") (name "/ADC_VCMO") (class "Default")
      (node (ref "C24") (pin "2") (pinfunction "2_2") (pintype "passive"))
      (node (ref "C59") (pin "2") (pinfunction "2_2") (pintype "passive"))
      (node (ref "C8") (pin "2") (pinfunction "2_2") (pintype "passive"))
      (node (ref "U1") (pin "7") (pinfunction "VOCM_7") (pintype "passive"))
      (node (ref "U4") (pin "7") (pinfunction "VOCM_7") (pintype "passive"))
      (node (ref "U7") (pin "10") (pinfunction "VCM_10") (pintype "passive"))
    )
    (net (code "35") (name "/ADOF_N") (class "Default")
      (node (ref "J1") (pin "19") (pinfunction "Y17_19") (pintype "passive"))
      (node (ref "U7") (pin "22") (pinfunction "OFN_22") (pintype "passive"))
    )
    (net (code "36") (name "/ADOF_P") (class "Default")
      (node (ref "J1") (pin "20") (pinfunction "Y16_20") (pintype "passive"))
      (node (ref "U7") (pin "23") (pinfunction "OFP_23") (pintype "passive"))
    )
    (net (code "37") (name "/AD_ICLK_C_N") (class "Default")
      (node (ref "C56") (pin "2") (pinfunction "2_2") (pintype "passive"))
      (node (ref "U7") (pin "20") (pinfunction "CLKN_20") (pintype "passive"))
    )
    (net (code "38") (name "/AD_ICLK_C_P") (class "Default")
      (node (ref "C58") (pin "2") (pinfunction "2_2") (pintype "passive"))
      (node (ref "U7") (pin "19") (pinfunction "CLKP_19") (pintype "passive"))
    )
    (net (code "39") (name "/AD_ICLK_N") (class "Default")
      (node (ref "C56") (pin "1") (pinfunction "1_1") (pintype "passive"))
      (node (ref "J1") (pin "25") (pinfunction "U15_25") (pintype "passive"))
      (node (ref "R34") (pin "1") (pinfunction "1_1") (pintype "passive"))
    )
    (net (code "40") (name "/AD_ICLK_P") (class "Default")
      (node (ref "C58") (pin "1") (pinfunction "1_1") (pintype "passive"))
      (node (ref "J1") (pin "26") (pinfunction "U14_26") (pintype "passive"))
      (node (ref "R34") (pin "2") (pinfunction "2_2") (pintype "passive"))
    )
    (net (code "41") (name "/AD_OCLK_N") (class "Default")
      (node (ref "J1") (pin "23") (pinfunction "U19_23") (pintype "passive"))
      (node (ref "U7") (pin "40") (pinfunction "CLKOUTN_40") (pintype "passive"))
    )
    (net (code "42") (name "/AD_OCLK_P") (class "Default")
      (node (ref "J1") (pin "24") (pinfunction "U18_24") (pintype "passive"))
      (node (ref "U7") (pin "41") (pinfunction "CLKOUTP_41") (pintype "passive"))
    )
    (net (code "43") (name "/AD_SCLK") (class "Default")
      (node (ref "J1") (pin "75") (pinfunction "W16_75") (pintype "passive"))
      (node (ref "U7") (pin "61") (pinfunction "SPI_SCLK_61") (pintype "input"))
    )
    (net (code "44") (name "/AD_SDATA") (class "Default")
      (node (ref "J1") (pin "79") (pinfunction "P16_79") (pintype "passive"))
      (node (ref "U7") (pin "60") (pinfunction "SPI_MOSI_60") (pintype "input"))
    )
    (net (code "45") (name "/AD_SDOUT") (class "Default")
      (node (ref "J1") (pin "77") (pinfunction "R17_77") (pintype "passive"))
      (node (ref "R27") (pin "1") (pinfunction "1_1") (pintype "passive"))
      (node (ref "R29") (pin "2") (pinfunction "2_2") (pintype "passive"))
    )
    (net (code "46") (name "/AD_SDOUT_R") (class "Default")
      (node (ref "R27") (pin "2") (pinfunction "2_2") (pintype "passive"))
      (node (ref "U7") (pin "59") (pinfunction "SPI_MISO_59") (pintype "open_collector"))
    )
    (net (code "47") (name "/AD_SEN") (class "Default")
      (node (ref "J1") (pin "73") (pinfunction "W19_73") (pintype "passive"))
      (node (ref "U7") (pin "62") (pinfunction "SPI_CS_62") (pintype "input"))
    )
    (net (code "48") (name "/CH1_N") (class "Default")
      (node (ref "R17") (pin "1") (pinfunction "1_1") (pintype "passive"))
      (node (ref "R20") (pin "2") (pinfunction "2_2") (pintype "passive"))
      (node (ref "U6") (pin "5") (pinfunction "IN-_5") (pintype "passive"))
    )
    (net (code "49") (name "/CH1_OUT_N") (class "Default")
      (node (ref "R19") (pin "1") (pinfunction "1_1") (pintype "passive"))
      (node (ref "U6") (pin "12") (pinfunction "OUT-_12") (pintype "passive"))
    )
    (net (code "50") (name "/CH1_OUT_P") (class "Default")
      (node (ref "R22") (pin "1") (pinfunction "1_1") (pintype "passive"))
      (node (ref "U6") (pin "13") (pinfunction "OUT+_13") (pintype "passive"))
    )
    (net (code "51") (name "/CH1_OUT_R_N") (class "Default")
      (node (ref "R19") (pin "2") (pinfunction "2_2") (pintype "passive"))
      (node (ref "U4") (pin "3") (pinfunction "INM_3") (pintype "passive"))
    )
    (net (code "52") (name "/CH1_OUT_R_P") (class "Default")
      (node (ref "R22") (pin "2") (pinfunction "2_2") (pintype "passive"))
      (node (ref "U4") (pin "2") (pinfunction "INP_2") (pintype "passive"))
    )
    (net (code "53") (name "/CH1_P") (class "Default")
      (node (ref "R23") (pin "1") (pinfunction "1_1") (pintype "passive"))
      (node (ref "R24") (pin "1") (pinfunction "1_1") (pintype "passive"))
      (node (ref "U6") (pin "6") (pinfunction "IN+_6") (pintype "passive"))
    )
    (net (code "54") (name "/CH2_N") (class "Default")
      (node (ref "R5") (pin "1") (pinfunction "1_1") (pintype "passive"))
      (node (ref "R8") (pin "2") (pinfunction "2_2") (pintype "passive"))
      (node (ref "U2") (pin "5") (pinfunction "IN-_5") (pintype "passive"))
    )
    (net (code "55") (name "/CH2_OUT_N") (class "Default")
      (node (ref "R7") (pin "1") (pinfunction "1_1") (pintype "passive"))
      (node (ref "U2") (pin "12") (pinfunction "OUT-_12") (pintype "passive"))
    )
    (net (code "56") (name "/CH2_OUT_P") (class "Default")
      (node (ref "R9") (pin "1") (pinfunction "1_1") (pintype "passive"))
      (node (ref "U2") (pin "13") (pinfunction "OUT+_13") (pintype "passive"))
    )
    (net (code "57") (name "/CH2_OUT_R_N") (class "Default")
      (node (ref "R7") (pin "2") (pinfunction "2_2") (pintype "passive"))
      (node (ref "U1") (pin "3") (pinfunction "INM_3") (pintype "passive"))
    )
    (net (code "58") (name "/CH2_OUT_R_P") (class "Default")
      (node (ref "R9") (pin "2") (pinfunction "2_2") (pintype "passive"))
      (node (ref "U1") (pin "2") (pinfunction "INP_2") (pintype "passive"))
    )
    (net (code "59") (name "/CH2_P") (class "Default")
      (node (ref "R10") (pin "1") (pinfunction "1_1") (pintype "passive"))
      (node (ref "R11") (pin "1") (pinfunction "1_1") (pintype "passive"))
      (node (ref "U2") (pin "6") (pinfunction "IN+_6") (pintype "passive"))
    )
    (net (code "60") (name "/INA_N") (class "Default")
      (node (ref "C23") (pin "1") (pinfunction "1_1") (pintype "passive"))
      (node (ref "R15") (pin "2") (pinfunction "2_2") (pintype "passive"))
      (node (ref "U7") (pin "5") (pinfunction "INM_A_5") (pintype "passive"))
    )
    (net (code "61") (name "/INA_P") (class "Default")
      (node (ref "C23") (pin "2") (pinfunction "2_2") (pintype "passive"))
      (node (ref "R18") (pin "2") (pinfunction "2_2") (pintype "passive"))
      (node (ref "U7") (pin "4") (pinfunction "INP_A_4") (pintype "passive"))
    )
    (net (code "62") (name "/INA_R_N") (class "Default")
      (node (ref "R15") (pin "1") (pinfunction "1_1") (pintype "passive"))
      (node (ref "U4") (pin "10") (pinfunction "OUTM_10") (pintype "passive"))
    )
    (net (code "63") (name "/INA_R_P") (class "Default")
      (node (ref "R18") (pin "1") (pinfunction "1_1") (pintype "passive"))
      (node (ref "U4") (pin "11") (pinfunction "OUTP_11") (pintype "passive"))
    )
    (net (code "64") (name "/INB_N") (class "Default")
      (node (ref "C7") (pin "1") (pinfunction "1_1") (pintype "passive"))
      (node (ref "R3") (pin "2") (pinfunction "2_2") (pintype "passive"))
      (node (ref "U7") (pin "12") (pinfunction "INM_B_12") (pintype "passive"))
    )
    (net (code "65") (name "/INB_P") (class "Default")
      (node (ref "C7") (pin "2") (pinfunction "2_2") (pintype "passive"))
      (node (ref "R6") (pin "2") (pinfunction "2_2") (pintype "passive"))
      (node (ref "U7") (pin "13") (pinfunction "INP_B_13") (pintype "passive"))
    )
    (net (code "66") (name "/INB_R_N") (class "Default")
      (node (ref "R3") (pin "1") (pinfunction "1_1") (pintype "passive"))
      (node (ref "U1") (pin "10") (pinfunction "OUTM_10") (pintype "passive"))
    )
    (net (code "67") (name "/INB_R_P") (class "Default")
      (node (ref "R6") (pin "1") (pinfunction "1_1") (pintype "passive"))
      (node (ref "U1") (pin "11") (pinfunction "OUTP_11") (pintype "passive"))
    )
    (net (code "68") (name "/LMH_CS0") (class "Default")
      (node (ref "J1") (pin "74") (pinfunction "W18_74") (pintype "passive"))
      (node (ref "U4") (pin "15") (pinfunction "~{CS}_15") (pintype "passive"))
    )
    (net (code "69") (name "/LMH_CS1") (class "Default")
      (node (ref "J1") (pin "72") (pinfunction "V17_72") (pintype "passive"))
      (node (ref "U1") (pin "15") (pinfunction "~{CS}_15") (pintype "passive"))
    )
    (net (code "70") (name "/LMH_SCK") (class "Default")
      (node (ref "J1") (pin "76") (pinfunction "V16_76") (pintype "passive"))
      (node (ref "U1") (pin "14") (pinfunction "SCLK_14") (pintype "passive"))
      (node (ref "U4") (pin "14") (pinfunction "SCLK_14") (pintype "passive"))
    )
    (net (code "71") (name "/LMH_SDI") (class "Default")
      (node (ref "J1") (pin "80") (pinfunction "P15_80") (pintype "passive"))
      (node (ref "U1") (pin "1") (pinfunction "SDI_1") (pintype "passive"))
      (node (ref "U4") (pin "1") (pinfunction "SDI_1") (pintype "passive"))
    )
    (net (code "72") (name "/LMH_SDO") (class "Default")
      (node (ref "J1") (pin "78") (pinfunction "R16_78") (pintype "passive"))
      (node (ref "R13") (pin "1") (pinfunction "1_1") (pintype "passive"))
      (node (ref "R2") (pin "1") (pinfunction "1_1") (pintype "passive"))
    )
    (net (code "73") (name "/LMH_SDO0") (class "Default")
      (node (ref "R13") (pin "2") (pinfunction "2_2") (pintype "passive"))
      (node (ref "U4") (pin "4") (pinfunction "SDO_4") (pintype "passive"))
    )
    (net (code "74") (name "/LMH_SDO1") (class "Default")
      (node (ref "R2") (pin "2") (pinfunction "2_2") (pintype "passive"))
      (node (ref "U1") (pin "4") (pinfunction "SDO_4") (pintype "passive"))
    )
    (net (code "75") (name "3V3") (class "Default")
      (node (ref "B1") (pin "3") (pinfunction "VIN_3") (pintype "power_in"))
      (node (ref "B2") (pin "3") (pinfunction "VIN_3") (pintype "power_in"))
      (node (ref "C15") (pin "2") (pinfunction "2_2") (pintype "passive"))
      (node (ref "C25") (pin "2") (pinfunction "2_2") (pintype "passive"))
      (node (ref "C48") (pin "2") (pinfunction "2_2") (pintype "passive"))
      (node (ref "C49") (pin "2") (pinfunction "2_2") (pintype "passive"))
      (node (ref "C51") (pin "2") (pinfunction "2_2") (pintype "passive"))
      (node (ref "C52") (pin "2") (pinfunction "2_2") (pintype "passive"))
      (node (ref "C63") (pin "2") (pinfunction "2_2") (pintype "passive"))
      (node (ref "C64") (pin "2") (pinfunction "2_2") (pintype "passive"))
      (node (ref "C66") (pin "2") (pinfunction "2_2") (pintype "passive"))
      (node (ref "C67") (pin "2") (pinfunction "2_2") (pintype "passive"))
      (node (ref "POWER") (pin "1") (pinfunction "1_1") (pintype "passive"))
      (node (ref "R12") (pin "2") (pinfunction "2_2") (pintype "passive"))
      (node (ref "R21") (pin "2") (pinfunction "2_2") (pintype "passive"))
      (node (ref "R30") (pin "1") (pinfunction "1_1") (pintype "passive"))
      (node (ref "R31") (pin "1") (pinfunction "1_1") (pintype "passive"))
      (node (ref "R33") (pin "1") (pinfunction "1_1") (pintype "passive"))
      (node (ref "R39") (pin "1") (pinfunction "1_1") (pintype "passive"))
      (node (ref "R40") (pin "1") (pinfunction "1_1") (pintype "passive"))
      (node (ref "R42") (pin "1") (pinfunction "1_1") (pintype "passive"))
      (node (ref "R43") (pin "1") (pinfunction "1_1") (pintype "passive"))
      (node (ref "U3") (pin "1") (pinfunction "IN_1") (pintype "passive"))
      (node (ref "U5") (pin "1") (pinfunction "IN_1") (pintype "passive"))
    )
    (net (code "76") (name "3V3_IN") (class "Default")
      (node (ref "J1") (pin "29") (pinfunction "3V3_29") (pintype "passive"))
      (node (ref "J1") (pin "69") (pinfunction "3V3_69") (pintype "passive"))
      (node (ref "POWER") (pin "2") (pinfunction "2_2") (pintype "passive"))
    )
    (net (code "77") (name "AGND") (class "Default")
      (node (ref "C1") (pin "1") (pinfunction "1_1") (pintype "passive"))
      (node (ref "C10") (pin "2") (pinfunction "2_2") (pintype "passive"))
      (node (ref "C11") (pin "2") (pinfunction "2_2") (pintype "passive"))
      (node (ref "C12") (pin "1") (pinfunction "1_1") (pintype "passive"))
      (node (ref "C13") (pin "2") (pinfunction "2_2") (pintype "passive"))
      (node (ref "C14") (pin "1") (pinfunction "1_1") (pintype "passive"))
      (node (ref "C17") (pin "1") (pinfunction "1_1") (pintype "passive"))
      (node (ref "C18") (pin "1") (pinfunction "1_1") (pintype "passive"))
      (node (ref "C19") (pin "2") (pinfunction "2_2") (pintype "passive"))
      (node (ref "C2") (pin "1") (pinfunction "1_1") (pintype "passive"))
      (node (ref "C20") (pin "1") (pinfunction "1_1") (pintype "passive"))
      (node (ref "C21") (pin "2") (pinfunction "2_2") (pintype "passive"))
      (node (ref "C22") (pin "1") (pinfunction "1_1") (pintype "passive"))
      (node (ref "C24") (pin "1") (pinfunction "1_1") (pintype "passive"))
      (node (ref "C27") (pin "2") (pinfunction "2_2") (pintype "passive"))
      (node (ref "C28") (pin "2") (pinfunction "2_2") (pintype "passive"))
      (node (ref "C29") (pin "2") (pinfunction "2_2") (pintype "passive"))
      (node (ref "C3") (pin "2") (pinfunction "2_2") (pintype "passive"))
      (node (ref "C30") (pin "1") (pinfunction "1_1") (pintype "passive"))
      (node (ref "C31") (pin "2") (pinfunction "2_2") (pintype "passive"))
      (node (ref "C32") (pin "1") (pinfunction "1_1") (pintype "passive"))
      (node (ref "C4") (pin "1") (pinfunction "1_1") (pintype "passive"))
      (node (ref "C40") (pin "1") (pinfunction "1_1") (pintype "passive"))
      (node (ref "C41") (pin "1") (pinfunction "1_1") (pintype "passive"))
      (node (ref "C42") (pin "1") (pinfunction "1_1") (pintype "passive"))
      (node (ref "C43") (pin "1") (pinfunction "1_1") (pintype "passive"))
      (node (ref "C44") (pin "1") (pinfunction "1_1") (pintype "passive"))
      (node (ref "C45") (pin "1") (pinfunction "1_1") (pintype "passive"))
      (node (ref "C46") (pin "1") (pinfunction "1_1") (pintype "passive"))
      (node (ref "C47") (pin "1") (pinfunction "1_1") (pintype "passive"))
      (node (ref "C5") (pin "2") (pinfunction "2_2") (pintype "passive"))
      (node (ref "C6") (pin "1") (pinfunction "1_1") (pintype "passive"))
      (node (ref "C8") (pin "1") (pinfunction "1_1") (pintype "passive"))
      (node (ref "C9") (pin "2") (pinfunction "2_2") (pintype "passive"))
      (node (ref "R1") (pin "1") (pinfunction "1_1") (pintype "passive"))
      (node (ref "R14") (pin "1") (pinfunction "1_1") (pintype "passive"))
      (node (ref "R44") (pin "2") (pinfunction "2_2") (pintype "passive"))
      (node (ref "R45") (pin "2") (pinfunction "2_2") (pintype "passive"))
      (node (ref "R46") (pin "2") (pinfunction "2_2") (pintype "passive"))
      (node (ref "U1") (pin "12") (pinfunction "GND_12") (pintype "passive"))
      (node (ref "U1") (pin "17") (pinfunction "EP_17") (pintype "passive"))
      (node (ref "U1") (pin "6") (pinfunction "PD_6") (pintype "passive"))
      (node (ref "U1") (pin "9") (pinfunction "GND_9") (pintype "passive"))
      (node (ref "U2") (pin "11") (pinfunction "GND_11") (pintype "passive"))
      (node (ref "U2") (pin "14") (pinfunction "GND_14") (pintype "passive"))
      (node (ref "U2") (pin "2") (pinfunction "VCM_2") (pintype "passive"))
      (node (ref "U4") (pin "12") (pinfunction "GND_12") (pintype "passive"))
      (node (ref "U4") (pin "17") (pinfunction "EP_17") (pintype "passive"))
      (node (ref "U4") (pin "6") (pinfunction "PD_6") (pintype "passive"))
      (node (ref "U4") (pin "9") (pinfunction "GND_9") (pintype "passive"))
      (node (ref "U6") (pin "11") (pinfunction "GND_11") (pintype "passive"))
      (node (ref "U6") (pin "14") (pinfunction "GND_14") (pintype "passive"))
      (node (ref "U6") (pin "2") (pinfunction "VCM_2") (pintype "passive"))
      (node (ref "U7") (pin "11") (pinfunction "GND_11") (pintype "passive"))
      (node (ref "U7") (pin "14") (pinfunction "GND_14") (pintype "passive"))
      (node (ref "U7") (pin "18") (pinfunction "GND_18") (pintype "passive"))
      (node (ref "U7") (pin "21") (pinfunction "GND_21") (pintype "passive"))
      (node (ref "U7") (pin "3") (pinfunction "GND_3") (pintype "passive"))
      (node (ref "U7") (pin "58") (pinfunction "GND_58") (pintype "passive"))
      (node (ref "U7") (pin "6") (pinfunction "GND_6") (pintype "passive"))
      (node (ref "U7") (pin "65") (pinfunction "GND_65") (pintype "passive"))
      (node (ref "U7") (pin "9") (pinfunction "GND_9") (pintype "passive"))
    )
    (net (code "78") (name "AVDD1V8_ADC") (class "Default")
      (node (ref "C26") (pin "2") (pinfunction "2_2") (pintype "passive"))
      (node (ref "C40") (pin "2") (pinfunction "2_2") (pintype "passive"))
      (node (ref "C41") (pin "2") (pinfunction "2_2") (pintype "passive"))
      (node (ref "C42") (pin "2") (pinfunction "2_2") (pintype "passive"))
      (node (ref "C43") (pin "2") (pinfunction "2_2") (pintype "passive"))
      (node (ref "C44") (pin "2") (pinfunction "2_2") (pintype "passive"))
      (node (ref "C45") (pin "2") (pinfunction "2_2") (pintype "passive"))
      (node (ref "C46") (pin "2") (pinfunction "2_2") (pintype "passive"))
      (node (ref "C47") (pin "2") (pinfunction "2_2") (pintype "passive"))
      (node (ref "C57") (pin "2") (pinfunction "2_2") (pintype "passive"))
      (node (ref "R35") (pin "2") (pinfunction "2_2") (pintype "passive"))
      (node (ref "U5") (pin "5") (pinfunction "OUT_5") (pintype "passive"))
      (node (ref "U7") (pin "1") (pinfunction "AVDD_1") (pintype "passive"))
      (node (ref "U7") (pin "15") (pinfunction "AVDD_15") (pintype "passive"))
      (node (ref "U7") (pin "16") (pinfunction "AVDD_16") (pintype "passive"))
      (node (ref "U7") (pin "17") (pinfunction "AVDD_17") (pintype "passive"))
      (node (ref "U7") (pin "2") (pinfunction "AVDD_2") (pintype "passive"))
      (node (ref "U7") (pin "64") (pinfunction "AVDD_64") (pintype "passive"))
    )
    (net (code "79") (name "DVDD1V8_ADC") (class "Default")
      (node (ref "C16") (pin "2") (pinfunction "2_2") (pintype "passive"))
      (node (ref "C33") (pin "2") (pinfunction "2_2") (pintype "passive"))
      (node (ref "C34") (pin "2") (pinfunction "2_2") (pintype "passive"))
      (node (ref "C35") (pin "2") (pinfunction "2_2") (pintype "passive"))
      (node (ref "C36") (pin "2") (pinfunction "2_2") (pintype "passive"))
      (node (ref "R29") (pin "1") (pinfunction "1_1") (pintype "passive"))
      (node (ref "U3") (pin "5") (pinfunction "OUT_5") (pintype "passive"))
      (node (ref "U7") (pin "32") (pinfunction "DVDD_32") (pintype "passive"))
      (node (ref "U7") (pin "49") (pinfunction "DVDD_49") (pintype "passive"))
    )
    (net (code "80") (name "GND") (class "Default")
      (node (ref "ADC-CH1") (pin "2") (pinfunction "GND_2") (pintype "passive"))
      (node (ref "ADC-CH2") (pin "2") (pinfunction "GND_2") (pintype "passive"))
      (node (ref "B1") (pin "13") (pinfunction "PAD_13") (pintype "passive"))
      (node (ref "B1") (pin "4") (pinfunction "GND_4") (pintype "passive"))
      (node (ref "B2") (pin "13") (pinfunction "PAD_13") (pintype "passive"))
      (node (ref "B2") (pin "4") (pinfunction "GND_4") (pintype "passive"))
      (node (ref "C15") (pin "1") (pinfunction "1_1") (pintype "passive"))
      (node (ref "C16") (pin "1") (pinfunction "1_1") (pintype "passive"))
      (node (ref "C25") (pin "1") (pinfunction "1_1") (pintype "passive"))
      (node (ref "C26") (pin "1") (pinfunction "1_1") (pintype "passive"))
      (node (ref "C33") (pin "1") (pinfunction "1_1") (pintype "passive"))
      (node (ref "C34") (pin "1") (pinfunction "1_1") (pintype "passive"))
      (node (ref "C35") (pin "1") (pinfunction "1_1") (pintype "passive"))
      (node (ref "C36") (pin "1") (pinfunction "1_1") (pintype "passive"))
      (node (ref "C37") (pin "1") (pinfunction "1_1") (pintype "passive"))
      (node (ref "C38") (pin "1") (pinfunction "1_1") (pintype "passive"))
      (node (ref "C39") (pin "1") (pinfunction "1_1") (pintype "passive"))
      (node (ref "C48") (pin "1") (pinfunction "1_1") (pintype "passive"))
      (node (ref "C49") (pin "1") (pinfunction "1_1") (pintype "passive"))
      (node (ref "C51") (pin "1") (pinfunction "1_1") (pintype "passive"))
      (node (ref "C52") (pin "1") (pinfunction "1_1") (pintype "passive"))
      (node (ref "C53") (pin "1") (pinfunction "1_1") (pintype "passive"))
      (node (ref "C54") (pin "1") (pinfunction "1_1") (pintype "passive"))
      (node (ref "C55") (pin "1") (pinfunction "1_1") (pintype "passive"))
      (node (ref "C57") (pin "1") (pinfunction "1_1") (pintype "passive"))
      (node (ref "C59") (pin "1") (pinfunction "1_1") (pintype "passive"))
      (node (ref "C60") (pin "1") (pinfunction "1_1") (pintype "passive"))
      (node (ref "C61") (pin "1") (pinfunction "1_1") (pintype "passive"))
      (node (ref "C62") (pin "1") (pinfunction "1_1") (pintype "passive"))
      (node (ref "C63") (pin "1") (pinfunction "1_1") (pintype "passive"))
      (node (ref "C64") (pin "1") (pinfunction "1_1") (pintype "passive"))
      (node (ref "C66") (pin "1") (pinfunction "1_1") (pintype "passive"))
      (node (ref "C67") (pin "1") (pinfunction "1_1") (pintype "passive"))
      (node (ref "C68") (pin "1") (pinfunction "1_1") (pintype "passive"))
      (node (ref "C69") (pin "1") (pinfunction "1_1") (pintype "passive"))
      (node (ref "J1") (pin "0") (pinfunction "GND_0") (pintype "passive"))
      (node (ref "J1") (pin "12") (pinfunction "GND_12") (pintype "passive"))
      (node (ref "J1") (pin "30") (pinfunction "GND_30") (pintype "passive"))
      (node (ref "J1") (pin "52") (pinfunction "GND_52") (pintype "passive"))
      (node (ref "J1") (pin "70") (pinfunction "GND_70") (pintype "passive"))
      (node (ref "LED1") (pin "2") (pinfunction "2_2") (pintype "passive"))
      (node (ref "POWER") (pin "0") (pinfunction "0_0") (pintype "passive"))
      (node (ref "R11") (pin "2") (pinfunction "2_2") (pintype "passive"))
      (node (ref "R16") (pin "2") (pinfunction "2_2") (pintype "passive"))
      (node (ref "R24") (pin "2") (pinfunction "2_2") (pintype "passive"))
      (node (ref "R25") (pin "1") (pinfunction "1_1") (pintype "passive"))
      (node (ref "R28") (pin "1") (pinfunction "1_1") (pintype "passive"))
      (node (ref "R36") (pin "1") (pinfunction "1_1") (pintype "passive"))
      (node (ref "R38") (pin "1") (pinfunction "1_1") (pintype "passive"))
      (node (ref "R4") (pin "2") (pinfunction "2_2") (pintype "passive"))
      (node (ref "R44") (pin "1") (pinfunction "1_1") (pintype "passive"))
      (node (ref "R45") (pin "1") (pinfunction "1_1") (pintype "passive"))
      (node (ref "R46") (pin "1") (pinfunction "1_1") (pintype "passive"))
      (node (ref "U3") (pin "2") (pinfunction "GND_2") (pintype "passive"))
      (node (ref "U5") (pin "2") (pinfunction "GND_2") (pintype "passive"))
      (node (ref "U7") (pin "33") (pinfunction "DGND_33") (pintype "passive"))
      (node (ref "U7") (pin "48") (pinfunction "DGND_48") (pintype "passive"))
      (node (ref "U7") (pin "63") (pinfunction "MODE_63") (pintype "passive"))
    )
    (net (code "81") (name "Net-(ADC-CH1-IN)") (class "Default")
      (node (ref "ADC-CH1") (pin "1") (pinfunction "IN_1") (pintype "passive"))
      (node (ref "R16") (pin "1") (pinfunction "1_1") (pintype "passive"))
      (node (ref "R20") (pin "1") (pinfunction "1_1") (pintype "passive"))
    )
    (net (code "82") (name "Net-(ADC-CH2-IN)") (class "Default")
      (node (ref "ADC-CH2") (pin "1") (pinfunction "IN_1") (pintype "passive"))
      (node (ref "R4") (pin "1") (pinfunction "1_1") (pintype "passive"))
      (node (ref "R8") (pin "1") (pinfunction "1_1") (pintype "passive"))
    )
    (net (code "83") (name "Net-(B1-C1+)") (class "Default")
      (node (ref "B1") (pin "10") (pinfunction "C1+_10") (pintype "power_in"))
      (node (ref "C50") (pin "2") (pinfunction "2_2") (pintype "passive"))
    )
    (net (code "84") (name "Net-(B1-C1-)") (class "Default")
      (node (ref "B1") (pin "9") (pinfunction "C1-_9") (pintype "power_in"))
      (node (ref "C50") (pin "1") (pinfunction "1_1") (pintype "passive"))
    )
    (net (code "85") (name "Net-(B1-CP)") (class "Default")
      (node (ref "B1") (pin "5") (pinfunction "CP_5") (pintype "power_in"))
      (node (ref "C37") (pin "2") (pinfunction "2_2") (pintype "passive"))
    )
    (net (code "86") (name "Net-(B1-EN+)") (class "Default")
      (node (ref "B1") (pin "12") (pinfunction "EN+_12") (pintype "passive"))
      (node (ref "R33") (pin "2") (pinfunction "2_2") (pintype "passive"))
    )
    (net (code "87") (name "Net-(B1-EN-)") (class "Default")
      (node (ref "B1") (pin "8") (pinfunction "EN-_8") (pintype "passive"))
      (node (ref "R31") (pin "2") (pinfunction "2_2") (pintype "passive"))
    )
    (net (code "88") (name "Net-(B1-FB+)") (class "Default")
      (node (ref "B1") (pin "2") (pinfunction "FB+_2") (pintype "power_in"))
      (node (ref "R28") (pin "2") (pinfunction "2_2") (pintype "passive"))
      (node (ref "R32") (pin "1") (pinfunction "1_1") (pintype "passive"))
    )
    (net (code "89") (name "Net-(B1-FB-)") (class "Default")
      (node (ref "B1") (pin "7") (pinfunction "FB-_7") (pintype "power_in"))
      (node (ref "R25") (pin "2") (pinfunction "2_2") (pintype "passive"))
      (node (ref "R26") (pin "1") (pinfunction "1_1") (pintype "passive"))
    )
    (net (code "90") (name "Net-(B1-PG)") (class "Default")
      (node (ref "B1") (pin "1") (pinfunction "PG_1") (pintype "passive"))
      (node (ref "R30") (pin "2") (pinfunction "2_2") (pintype "passive"))
    )
    (net (code "91") (name "Net-(B2-C1+)") (class "Default")
      (node (ref "B2") (pin "10") (pinfunction "C1+_10") (pintype "power_in"))
      (node (ref "C65") (pin "2") (pinfunction "2_2") (pintype "passive"))
    )
    (net (code "92") (name "Net-(B2-C1-)") (class "Default")
      (node (ref "B2") (pin "9") (pinfunction "C1-_9") (pintype "power_in"))
      (node (ref "C65") (pin "1") (pinfunction "1_1") (pintype "passive"))
    )
    (net (code "93") (name "Net-(B2-CP)") (class "Default")
      (node (ref "B2") (pin "5") (pinfunction "CP_5") (pintype "power_in"))
      (node (ref "C60") (pin "2") (pinfunction "2_2") (pintype "passive"))
    )
    (net (code "94") (name "Net-(B2-EN+)") (class "Default")
      (node (ref "B2") (pin "12") (pinfunction "EN+_12") (pintype "passive"))
      (node (ref "R42") (pin "2") (pinfunction "2_2") (pintype "passive"))
    )
    (net (code "95") (name "Net-(B2-EN-)") (class "Default")
      (node (ref "B2") (pin "8") (pinfunction "EN-_8") (pintype "passive"))
      (node (ref "R40") (pin "2") (pinfunction "2_2") (pintype "passive"))
    )
    (net (code "96") (name "Net-(B2-FB+)") (class "Default")
      (node (ref "B2") (pin "2") (pinfunction "FB+_2") (pintype "power_in"))
      (node (ref "R38") (pin "2") (pinfunction "2_2") (pintype "passive"))
      (node (ref "R41") (pin "1") (pinfunction "1_1") (pintype "passive"))
    )
    (net (code "97") (name "Net-(B2-FB-)") (class "Default")
      (node (ref "B2") (pin "7") (pinfunction "FB-_7") (pintype "power_in"))
      (node (ref "R36") (pin "2") (pinfunction "2_2") (pintype "passive"))
      (node (ref "R37") (pin "1") (pinfunction "1_1") (pintype "passive"))
    )
    (net (code "98") (name "Net-(B2-PG)") (class "Default")
      (node (ref "B2") (pin "1") (pinfunction "PG_1") (pintype "passive"))
      (node (ref "R39") (pin "2") (pinfunction "2_2") (pintype "passive"))
    )
    (net (code "99") (name "Net-(LED1-Pad1)") (class "Default")
      (node (ref "LED1") (pin "1") (pinfunction "1_1") (pintype "passive"))
      (node (ref "R43") (pin "2") (pinfunction "2_2") (pintype "passive"))
    )
    (net (code "100") (name "Net-(U2-FB+)") (class "Default")
      (node (ref "R5") (pin "2") (pinfunction "2_2") (pintype "passive"))
      (node (ref "U2") (pin "4") (pinfunction "FB+_4") (pintype "passive"))
    )
    (net (code "101") (name "Net-(U2-FB-)") (class "Default")
      (node (ref "R10") (pin "2") (pinfunction "2_2") (pintype "passive"))
      (node (ref "U2") (pin "7") (pinfunction "FB-_7") (pintype "passive"))
    )
    (net (code "102") (name "Net-(U2-VEN)") (class "Default")
      (node (ref "R1") (pin "2") (pinfunction "2_2") (pintype "passive"))
      (node (ref "U2") (pin "9") (pinfunction "VEN_9") (pintype "passive"))
    )
    (net (code "103") (name "Net-(U3-EN)") (class "Default")
      (node (ref "R12") (pin "1") (pinfunction "1_1") (pintype "passive"))
      (node (ref "U3") (pin "3") (pinfunction "EN_3") (pintype "passive"))
    )
    (net (code "104") (name "Net-(U5-EN)") (class "Default")
      (node (ref "R21") (pin "1") (pinfunction "1_1") (pintype "passive"))
      (node (ref "U5") (pin "3") (pinfunction "EN_3") (pintype "passive"))
    )
    (net (code "105") (name "Net-(U6-FB+)") (class "Default")
      (node (ref "R17") (pin "2") (pinfunction "2_2") (pintype "passive"))
      (node (ref "U6") (pin "4") (pinfunction "FB+_4") (pintype "passive"))
    )
    (net (code "106") (name "Net-(U6-FB-)") (class "Default")
      (node (ref "R23") (pin "2") (pinfunction "2_2") (pintype "passive"))
      (node (ref "U6") (pin "7") (pinfunction "FB-_7") (pintype "passive"))
    )
    (net (code "107") (name "Net-(U6-VEN)") (class "Default")
      (node (ref "R14") (pin "2") (pinfunction "2_2") (pintype "passive"))
      (node (ref "U6") (pin "9") (pinfunction "VEN_9") (pintype "passive"))
    )
    (net (code "108") (name "Net-(U7B-VREF)") (class "Default")
      (node (ref "C55") (pin "2") (pinfunction "2_2") (pintype "passive"))
      (node (ref "U7") (pin "8") (pinfunction "VREF_8") (pintype "passive"))
    )
    (net (code "109") (name "unconnected-(J1A-5V-Pad11)") (class "Default")
      (node (ref "J1") (pin "11") (pinfunction "5V_11") (pintype "passive"))
    )
    (net (code "110") (name "unconnected-(J1A-R19-Pad9)") (class "Default")
      (node (ref "J1") (pin "9") (pinfunction "R19_9") (pintype "passive"))
    )
    (net (code "111") (name "unconnected-(J1A-T19-Pad10)") (class "Default")
      (node (ref "J1") (pin "10") (pinfunction "T19_10") (pintype "passive"))
    )
    (net (code "112") (name "unconnected-(J1B-5V-Pad51)") (class "Default")
      (node (ref "J1") (pin "51") (pinfunction "5V_51") (pintype "passive"))
    )
    (net (code "113") (name "unconnected-(J1B-F19-Pad48)") (class "Default")
      (node (ref "J1") (pin "48") (pinfunction "F19_48") (pintype "passive"))
    )
    (net (code "114") (name "unconnected-(J1B-F20-Pad47)") (class "Default")
      (node (ref "J1") (pin "47") (pinfunction "F20_47") (pintype "passive"))
    )
    (net (code "115") (name "unconnected-(J1B-G19-Pad46)") (class "Default")
      (node (ref "J1") (pin "46") (pinfunction "G19_46") (pintype "passive"))
    )
    (net (code "116") (name "unconnected-(J1B-G20-Pad45)") (class "Default")
      (node (ref "J1") (pin "45") (pinfunction "G20_45") (pintype "passive"))
    )
    (net (code "117") (name "unconnected-(J1B-H15-Pad42)") (class "Default")
      (node (ref "J1") (pin "42") (pinfunction "H15_42") (pintype "passive"))
    )
    (net (code "118") (name "unconnected-(J1B-H18-Pad49)") (class "Default")
      (node (ref "J1") (pin "49") (pinfunction "H18_49") (pintype "passive"))
    )
    (net (code "119") (name "unconnected-(J1B-H20-Pad55)") (class "Default")
      (node (ref "J1") (pin "55") (pinfunction "H20_55") (pintype "passive"))
    )
    (net (code "120") (name "unconnected-(J1B-J14-Pad43)") (class "Default")
      (node (ref "J1") (pin "43") (pinfunction "J14_43") (pintype "passive"))
    )
    (net (code "121") (name "unconnected-(J1B-J18-Pad50)") (class "Default")
      (node (ref "J1") (pin "50") (pinfunction "J18_50") (pintype "passive"))
    )
    (net (code "122") (name "unconnected-(J1B-J19-Pad53)") (class "Default")
      (node (ref "J1") (pin "53") (pinfunction "J19_53") (pintype "passive"))
    )
    (net (code "123") (name "unconnected-(J1B-J20-Pad56)") (class "Default")
      (node (ref "J1") (pin "56") (pinfunction "J20_56") (pintype "passive"))
    )
    (net (code "124") (name "unconnected-(J1B-K14-Pad44)") (class "Default")
      (node (ref "J1") (pin "44") (pinfunction "K14_44") (pintype "passive"))
    )
    (net (code "125") (name "unconnected-(J1B-K18-Pad41)") (class "Default")
      (node (ref "J1") (pin "41") (pinfunction "K18_41") (pintype "passive"))
    )
    (net (code "126") (name "unconnected-(J1B-K19-Pad54)") (class "Default")
      (node (ref "J1") (pin "54") (pinfunction "K19_54") (pintype "passive"))
    )
    (net (code "127") (name "unconnected-(J1B-L14-Pad58)") (class "Default")
      (node (ref "J1") (pin "58") (pinfunction "L14_58") (pintype "passive"))
    )
    (net (code "128") (name "unconnected-(J1B-L15-Pad57)") (class "Default")
      (node (ref "J1") (pin "57") (pinfunction "L15_57") (pintype "passive"))
    )
    (net (code "129") (name "unconnected-(J1B-L19-Pad62)") (class "Default")
      (node (ref "J1") (pin "62") (pinfunction "L19_62") (pintype "passive"))
    )
    (net (code "130") (name "unconnected-(J1B-L20-Pad61)") (class "Default")
      (node (ref "J1") (pin "61") (pinfunction "L20_61") (pintype "passive"))
    )
    (net (code "131") (name "unconnected-(J1B-N15-Pad64)") (class "Default")
      (node (ref "J1") (pin "64") (pinfunction "N15_64") (pintype "passive"))
    )
    (net (code "132") (name "unconnected-(J1B-N16-Pad63)") (class "Default")
      (node (ref "J1") (pin "63") (pinfunction "N16_63") (pintype "passive"))
    )
    (net (code "133") (name "unconnected-(J1B-N17-Pad66)") (class "Default")
      (node (ref "J1") (pin "66") (pinfunction "N17_66") (pintype "passive"))
    )
    (net (code "134") (name "unconnected-(J1B-NC-Pad59)") (class "Default")
      (node (ref "J1") (pin "59") (pinfunction "NC_59") (pintype "passive"))
    )
    (net (code "135") (name "unconnected-(J1B-NC-Pad60)") (class "Default")
      (node (ref "J1") (pin "60") (pinfunction "NC_60") (pintype "passive"))
    )
    (net (code "136") (name "unconnected-(J1B-P18-Pad65)") (class "Default")
      (node (ref "J1") (pin "65") (pinfunction "P18_65") (pintype "passive"))
    )
    (net (code "137") (name "unconnected-(J1B-R18-Pad67)") (class "Default")
      (node (ref "J1") (pin "67") (pinfunction "R18_67") (pintype "passive"))
    )
    (net (code "138") (name "unconnected-(J1B-T17-Pad68)") (class "Default")
      (node (ref "J1") (pin "68") (pinfunction "T17_68") (pintype "passive"))
    )
    (net (code "139") (name "unconnected-(J1B-V18-Pad71)") (class "Default")
      (node (ref "J1") (pin "71") (pinfunction "V18_71") (pintype "passive"))
    )
    (net (code "140") (name "unconnected-(POWER-Pad3)") (class "Default")
      (node (ref "POWER") (pin "3") (pinfunction "3_3") (pintype "passive+no_connect"))
    )
    (net (code "141") (name "unconnected-(U3-NC-Pad4)") (class "Default")
      (node (ref "U3") (pin "4") (pinfunction "NC_4") (pintype "passive+no_connect"))
    )
    (net (code "142") (name "unconnected-(U5-NC-Pad4)") (class "Default")
      (node (ref "U5") (pin "4") (pinfunction "NC_4") (pintype "passive+no_connect"))
    )
  )
)
